# lab1_patrusheva_usb_spi.net
KiCad netlist of a schematic drawn in Altium Designer
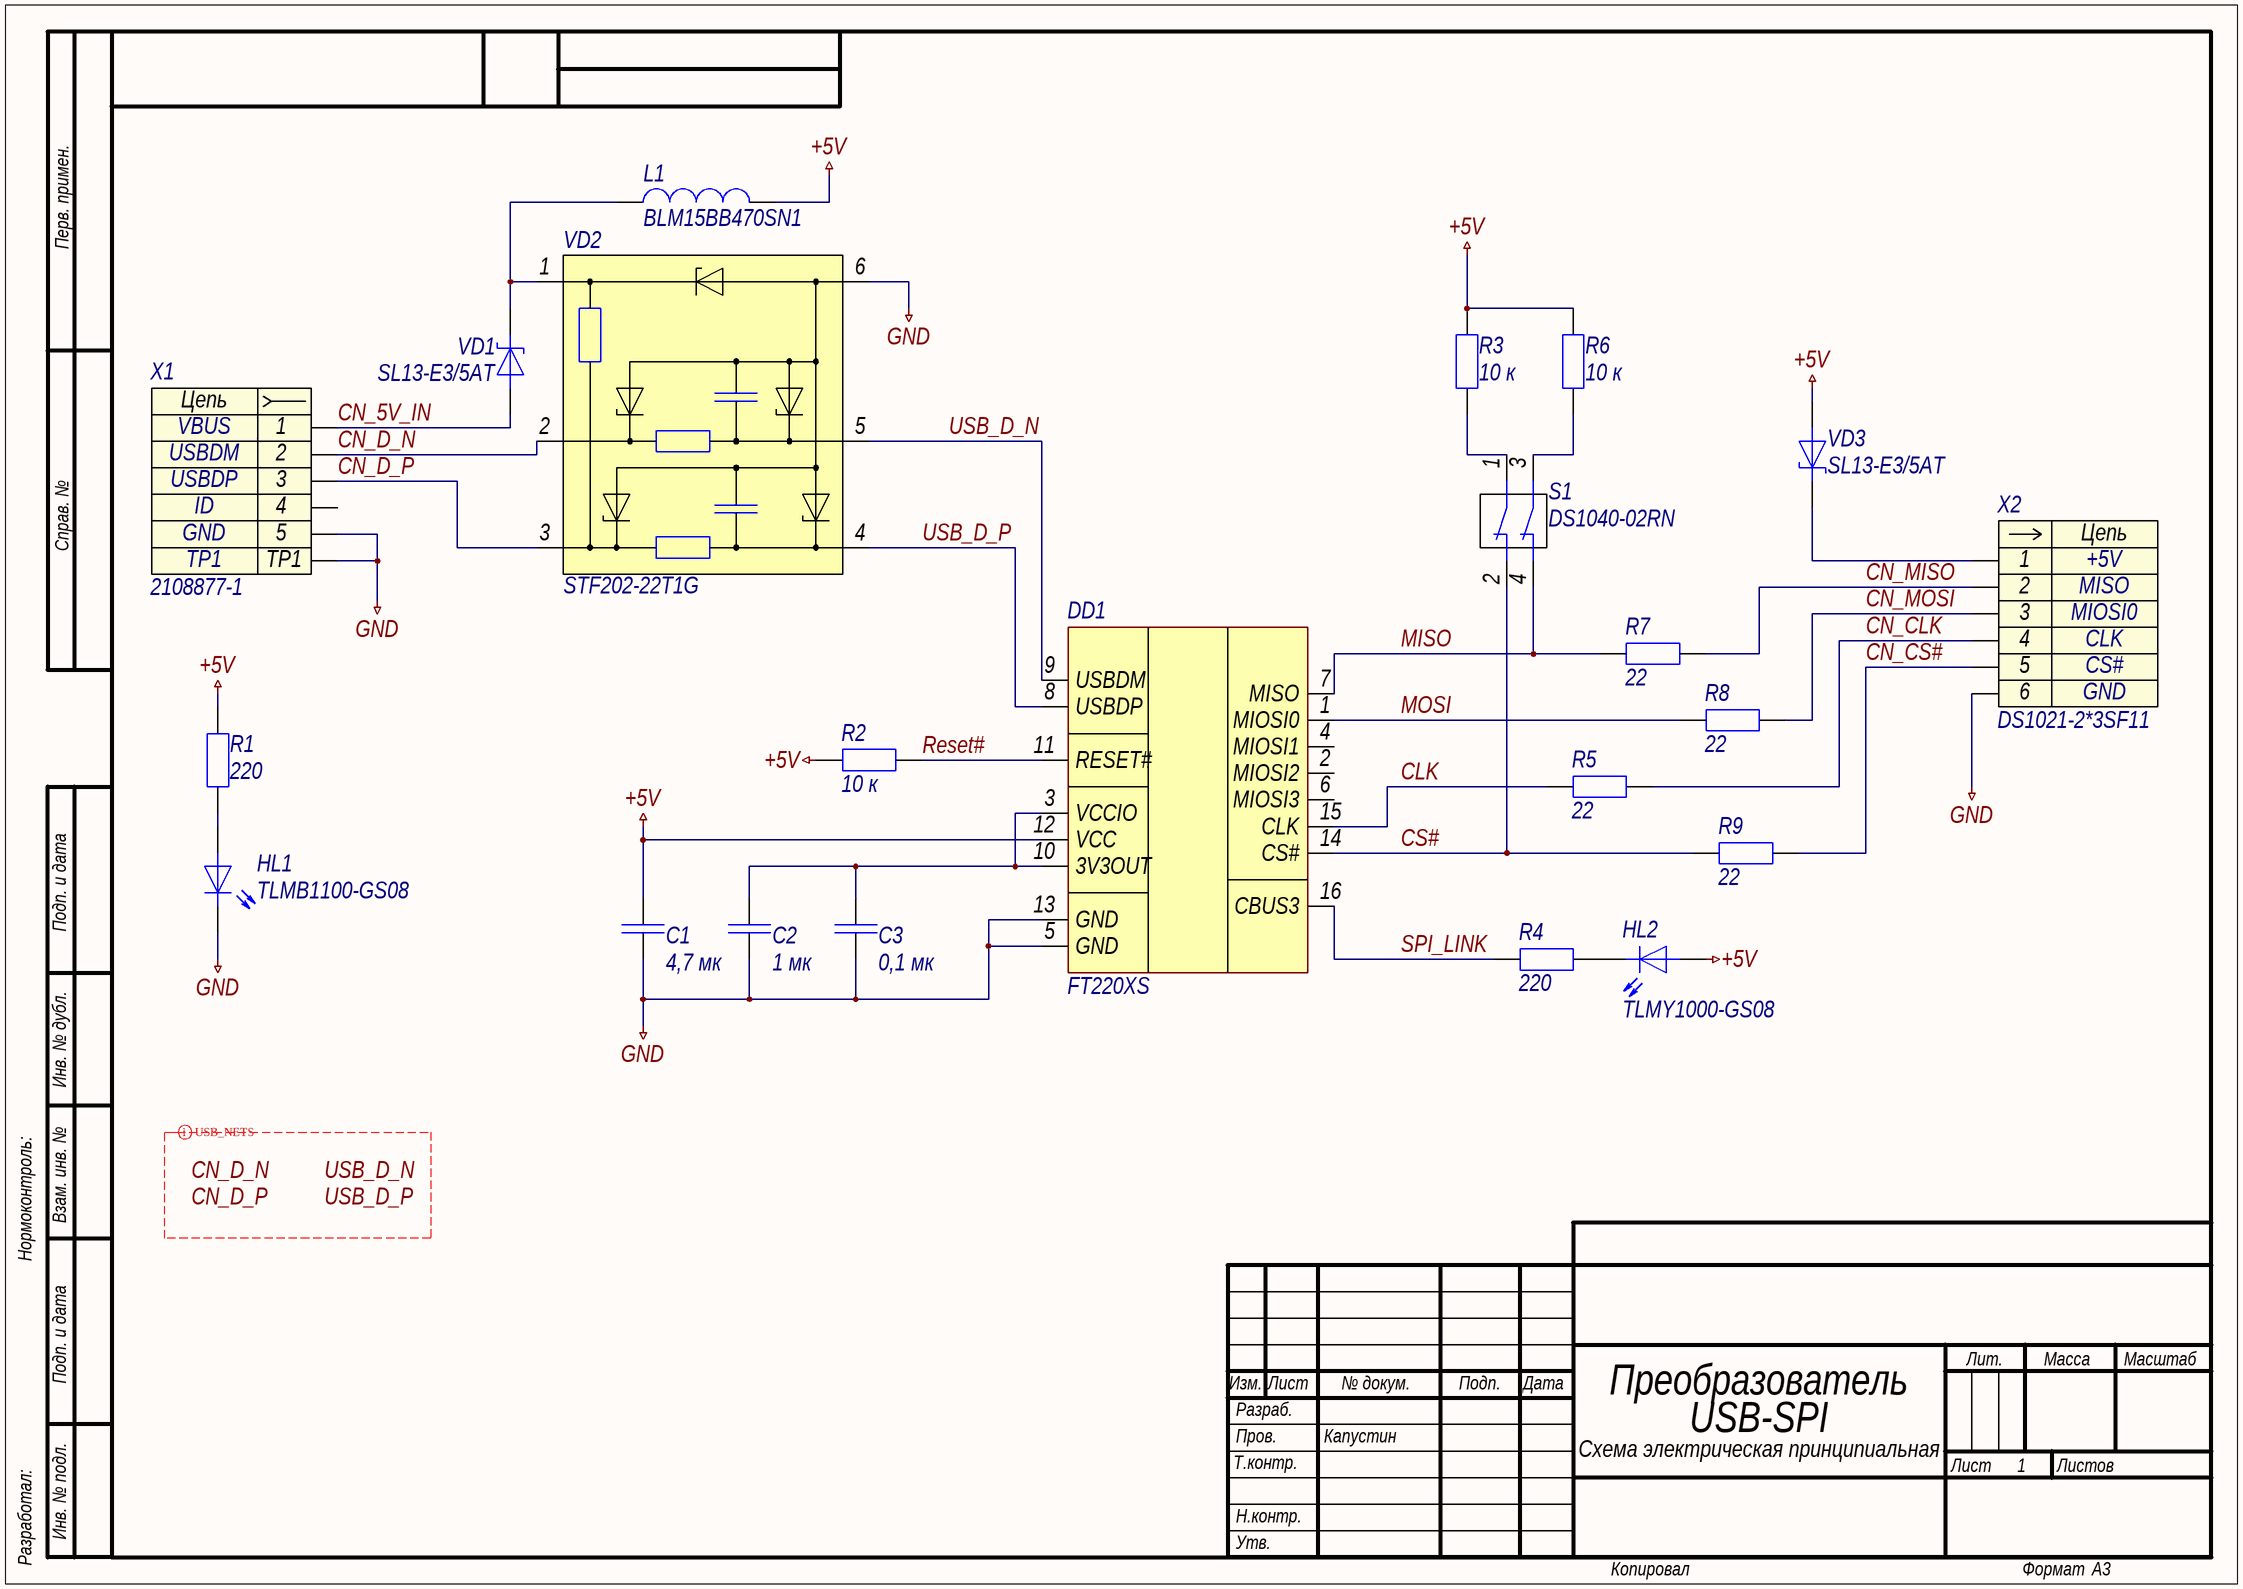
[diagram p0: lab1_patrusheva_usb_spi.SchDoc]

(export (version "E")
  (design (tool "Eeschema 10.0.6"))
  (components
    (comp (ref "C1")
      (value "4,7 мк")
      (footprint "C0603")
      (description "=Описание")
      (libsource (lib "Database_Students25") (part "C-NONPOLAR"))
    )
    (comp (ref "C2")
      (value "1 мк")
      (footprint "C0603")
      (description "=Описание")
      (libsource (lib "Database_Students25") (part "C-NONPOLAR"))
    )
    (comp (ref "C3")
      (value "0,1 мк")
      (footprint "C0603")
      (description "=Описание")
      (libsource (lib "Database_Students25") (part "C-NONPOLAR"))
    )
    (comp (ref "DD1")
      (value "FT220XS")
      (footprint "SSOP-16")
      (description "=Описание")
      (libsource (lib "Database_Students25") (part "FT220XS"))
    )
    (comp (ref "HL1")
      (value "TLMB1100-GS08")
      (footprint "HL0603")
      (description "=Описание")
      (libsource (lib "Database_Students25") (part "HL-COMMON"))
    )
    (comp (ref "HL2")
      (value "TLMY1000-GS08")
      (footprint "HL0603")
      (description "=Описание")
      (libsource (lib "Database_Students25") (part "HL-COMMON"))
    )
    (comp (ref "L1")
      (value "BLM15BB470SN1")
      (footprint "BLM31PG330SN1")
      (description "=Описание")
      (libsource (lib "Database_Students25") (part "I-47Ohms"))
    )
    (comp (ref "R1")
      (value "220")
      (footprint "R0603")
      (description "=Описание")
      (libsource (lib "Database_Students25") (part "R-COMMON"))
    )
    (comp (ref "R2")
      (value "10 к")
      (footprint "R0603")
      (description "=Описание")
      (libsource (lib "Database_Students25") (part "R-COMMON"))
    )
    (comp (ref "R3")
      (value "10 к")
      (footprint "R0603")
      (description "=Описание")
      (libsource (lib "Database_Students25") (part "R-COMMON"))
    )
    (comp (ref "R4")
      (value "220")
      (footprint "R0603")
      (description "=Описание")
      (libsource (lib "Database_Students25") (part "R-COMMON"))
    )
    (comp (ref "R5")
      (value "22")
      (footprint "R0603")
      (description "=Описание")
      (libsource (lib "Database_Students25") (part "R-COMMON"))
    )
    (comp (ref "R6")
      (value "10 к")
      (footprint "R0603")
      (description "=Описание")
      (libsource (lib "Database_Students25") (part "R-COMMON"))
    )
    (comp (ref "R7")
      (value "22")
      (footprint "R0603")
      (description "=Описание")
      (libsource (lib "Database_Students25") (part "R-COMMON"))
    )
    (comp (ref "R8")
      (value "22")
      (footprint "R0603")
      (description "=Описание")
      (libsource (lib "Database_Students25") (part "R-COMMON"))
    )
    (comp (ref "R9")
      (value "22")
      (footprint "R0603")
      (description "=Описание")
      (libsource (lib "Database_Students25") (part "R-COMMON"))
    )
    (comp (ref "S1")
      (value "DS1040-02RN")
      (footprint "DS1040-02RN:DS1040-02RN")
      (libsource (lib "DS1040-02RN") (part "Component_1"))
    )
    (comp (ref "VD1")
      (value "SL13-E3/5AT")
      (footprint "DO-214AC")
      (description "=Описание")
      (libsource (lib "Database_Students25") (part "DIODE-SCHOTTKY"))
    )
    (comp (ref "VD2")
      (value "STF202-22T1G")
      (footprint "tsop-6")
      (description "=Описание")
      (libsource (lib "Database_Students25") (part "STF202-22T1G"))
    )
    (comp (ref "VD3")
      (value "SL13-E3/5AT")
      (footprint "DO-214AC")
      (description "=Описание")
      (libsource (lib "") (part "DIODE-SCHOTTKY_1"))
    )
    (comp (ref "X1")
      (value "2108877-1")
      (footprint "2108877-1")
      (libsource (lib "Database_Students25") (part "HEADER-5-TP1-SCT"))
    )
    (comp (ref "X2")
      (value "DS1021-2*3SF11")
      (footprint "DS1021-2X3SF11")
      (libsource (lib "Database_Students25") (part "HEADER-6-PLG"))
    )
  )
  (nets
    (net (code "1") (name "+5V") (class "Default")
      (node (ref "C1") (pin "2") (pinfunction "2_2") (pintype "passive"))
      (node (ref "DD1") (pin "12") (pinfunction "VCC_12") (pintype "passive"))
      (node (ref "HL2") (pin "2") (pinfunction "2_2") (pintype "passive"))
      (node (ref "L1") (pin "2") (pinfunction "2_2") (pintype "passive"))
      (node (ref "R1") (pin "2") (pinfunction "2_2") (pintype "passive"))
      (node (ref "R2") (pin "1") (pinfunction "1_1") (pintype "passive"))
      (node (ref "R3") (pin "2") (pinfunction "2_2") (pintype "passive"))
      (node (ref "R6") (pin "2") (pinfunction "2_2") (pintype "passive"))
      (node (ref "VD3") (pin "2") (pinfunction "2_2") (pintype "passive"))
    )
    (net (code "2") (name "/CLK") (class "Default")
      (node (ref "DD1") (pin "15") (pinfunction "CLK_15") (pintype "passive"))
      (node (ref "R5") (pin "1") (pinfunction "1_1") (pintype "passive"))
    )
    (net (code "3") (name "/CN_5V_IN") (class "Default")
      (node (ref "VD1") (pin "1") (pinfunction "1_1") (pintype "passive"))
      (node (ref "X1") (pin "1") (pinfunction "1_1") (pintype "passive"))
    )
    (net (code "4") (name "/CN_CLK") (class "Default")
      (node (ref "R5") (pin "2") (pinfunction "2_2") (pintype "passive"))
      (node (ref "X2") (pin "4") (pinfunction "4_4") (pintype "passive"))
    )
    (net (code "5") (name "/CN_CS#") (class "Default")
      (node (ref "R9") (pin "2") (pinfunction "2_2") (pintype "passive"))
      (node (ref "X2") (pin "5") (pinfunction "5_5") (pintype "passive"))
    )
    (net (code "6") (name "/CN_D_N") (class "Default")
      (node (ref "VD2") (pin "2") (pinfunction "2_2") (pintype "passive"))
      (node (ref "X1") (pin "2") (pinfunction "2_2") (pintype "passive"))
    )
    (net (code "7") (name "/CN_D_P") (class "Default")
      (node (ref "VD2") (pin "3") (pinfunction "3_3") (pintype "passive"))
      (node (ref "X1") (pin "3") (pinfunction "3_3") (pintype "passive"))
    )
    (net (code "8") (name "/CN_MISO") (class "Default")
      (node (ref "R7") (pin "2") (pinfunction "2_2") (pintype "passive"))
      (node (ref "X2") (pin "2") (pinfunction "2_2") (pintype "passive"))
    )
    (net (code "9") (name "/CN_MOSI") (class "Default")
      (node (ref "R8") (pin "2") (pinfunction "2_2") (pintype "passive"))
      (node (ref "X2") (pin "3") (pinfunction "3_3") (pintype "passive"))
    )
    (net (code "10") (name "/CS#") (class "Default")
      (node (ref "DD1") (pin "14") (pinfunction "CS#_14") (pintype "passive"))
      (node (ref "R9") (pin "1") (pinfunction "1_1") (pintype "passive"))
      (node (ref "S1") (pin "2") (pinfunction "2_2") (pintype "passive"))
    )
    (net (code "11") (name "/MISO") (class "Default")
      (node (ref "DD1") (pin "7") (pinfunction "MISO_7") (pintype "passive"))
      (node (ref "R7") (pin "1") (pinfunction "1_1") (pintype "passive"))
      (node (ref "S1") (pin "4") (pinfunction "4_4") (pintype "passive"))
    )
    (net (code "12") (name "/MOSI") (class "Default")
      (node (ref "DD1") (pin "1") (pinfunction "MIOSI0_1") (pintype "passive"))
      (node (ref "R8") (pin "1") (pinfunction "1_1") (pintype "passive"))
    )
    (net (code "13") (name "/Reset#") (class "Default")
      (node (ref "DD1") (pin "11") (pinfunction "RESET#_11") (pintype "passive"))
      (node (ref "R2") (pin "2") (pinfunction "2_2") (pintype "passive"))
    )
    (net (code "14") (name "/SPI_LINK") (class "Default")
      (node (ref "DD1") (pin "16") (pinfunction "CBUS3_16") (pintype "passive"))
      (node (ref "R4") (pin "1") (pinfunction "1_1") (pintype "passive"))
    )
    (net (code "15") (name "/USB_D_N") (class "Default")
      (node (ref "DD1") (pin "9") (pinfunction "USBDM_9") (pintype "passive"))
      (node (ref "VD2") (pin "5") (pinfunction "5_5") (pintype "passive"))
    )
    (net (code "16") (name "/USB_D_P") (class "Default")
      (node (ref "DD1") (pin "8") (pinfunction "USBDP_8") (pintype "passive"))
      (node (ref "VD2") (pin "4") (pinfunction "4_4") (pintype "passive"))
    )
    (net (code "17") (name "GND") (class "Default")
      (node (ref "C1") (pin "1") (pinfunction "1_1") (pintype "passive"))
      (node (ref "C2") (pin "1") (pinfunction "1_1") (pintype "passive"))
      (node (ref "C3") (pin "1") (pinfunction "1_1") (pintype "passive"))
      (node (ref "DD1") (pin "13") (pinfunction "GND_13") (pintype "passive"))
      (node (ref "DD1") (pin "5") (pinfunction "GND_5") (pintype "passive"))
      (node (ref "HL1") (pin "1") (pinfunction "1_1") (pintype "passive"))
      (node (ref "VD2") (pin "6") (pinfunction "6_6") (pintype "passive"))
      (node (ref "X1") (pin "5") (pinfunction "5_5") (pintype "passive"))
      (node (ref "X1") (pin "TP1") (pinfunction "TP1_TP1") (pintype "passive"))
      (node (ref "X2") (pin "6") (pinfunction "6_6") (pintype "passive"))
    )
    (net (code "18") (name "Net-(DD1-3V3OUT)") (class "Default")
      (node (ref "C2") (pin "2") (pinfunction "2_2") (pintype "passive"))
      (node (ref "C3") (pin "2") (pinfunction "2_2") (pintype "passive"))
      (node (ref "DD1") (pin "10") (pinfunction "3V3OUT_10") (pintype "passive"))
      (node (ref "DD1") (pin "3") (pinfunction "VCCIO_3") (pintype "passive"))
    )
    (net (code "19") (name "Net-(HL1-Pad2)") (class "Default")
      (node (ref "HL1") (pin "2") (pinfunction "2_2") (pintype "passive"))
      (node (ref "R1") (pin "1") (pinfunction "1_1") (pintype "passive"))
    )
    (net (code "20") (name "Net-(HL2-Pad1)") (class "Default")
      (node (ref "HL2") (pin "1") (pinfunction "1_1") (pintype "passive"))
      (node (ref "R4") (pin "2") (pinfunction "2_2") (pintype "passive"))
    )
    (net (code "21") (name "Net-(L1-Pad1)") (class "Default")
      (node (ref "L1") (pin "1") (pinfunction "1_1") (pintype "passive"))
      (node (ref "VD1") (pin "1") (pinfunction "1_1") (pintype "passive"))
      (node (ref "VD2") (pin "1") (pinfunction "1_1") (pintype "passive"))
    )
    (net (code "22") (name "Net-(R3-Pad1)") (class "Default")
      (node (ref "R3") (pin "1") (pinfunction "1_1") (pintype "passive"))
      (node (ref "S1") (pin "1") (pinfunction "1_1") (pintype "passive"))
    )
    (net (code "23") (name "Net-(R6-Pad1)") (class "Default")
      (node (ref "R6") (pin "1") (pinfunction "1_1") (pintype "passive"))
      (node (ref "S1") (pin "3") (pinfunction "3_3") (pintype "passive"))
    )
    (net (code "24") (name "Net-(VD3-Pad1)") (class "Default")
      (node (ref "VD3") (pin "1") (pinfunction "1_1") (pintype "passive"))
      (node (ref "X2") (pin "1") (pinfunction "1_1") (pintype "passive"))
    )
    (net (code "25") (name "unconnected-(DD1-MIOSI1-Pad4)") (class "Default")
      (node (ref "DD1") (pin "4") (pinfunction "MIOSI1_4") (pintype "passive"))
    )
    (net (code "26") (name "unconnected-(DD1-MIOSI2-Pad2)") (class "Default")
      (node (ref "DD1") (pin "2") (pinfunction "MIOSI2_2") (pintype "passive"))
    )
    (net (code "27") (name "unconnected-(DD1-MIOSI3-Pad6)") (class "Default")
      (node (ref "DD1") (pin "6") (pinfunction "MIOSI3_6") (pintype "passive"))
    )
    (net (code "28") (name "unconnected-(VD2-Pad2)") (class "Default")
      (node (ref "VD2") (pin "2") (pinfunction "2_2") (pintype "passive"))
    )
    (net (code "29") (name "unconnected-(X1-Pad4)") (class "Default")
      (node (ref "X1") (pin "4") (pinfunction "4_4") (pintype "passive"))
    )
  )
)
